# mic.net
KiCad netlist of a schematic drawn in Altium Designer
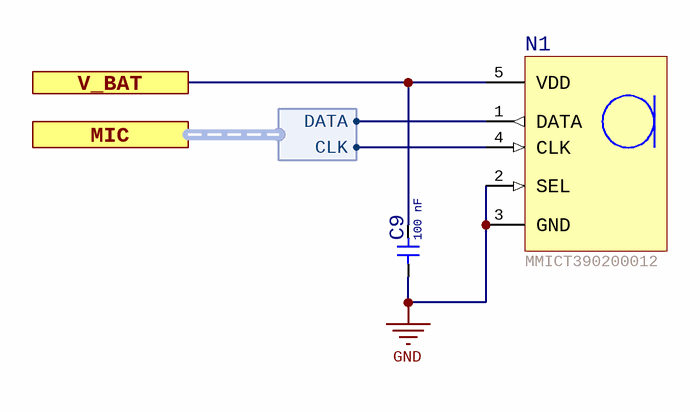
[diagram p0: mic.SchDoc]

(export (version "E")
  (design (tool "Eeschema 10.0.6"))
  (components
    (comp (ref "C9")
      (value "100 nF")
      (footprint "1608C")
      (description "SMD ceramic capacitor")
      (fields (field (name "MANUFACTURER") "Samsung") (field (name "VOLTAGE") "16"))
      (libsource (lib "Contronix") (part "CAP-NP"))
    )
    (comp (ref "N1")
      (value "SNS-MIC-T3902")
      (footprint "SNS-MIC-T3902")
      (description "Bottom Port PDM Low‐Power Multi‐Mode Microphone With High AOP Mode")
      (fields
        (field (name "MANUFACTURER P/N") "MMICT390200012")
        (field (name "MANUFACTURER") "InvenSense")
        (field (name "MANUFACTURER PART NUMBER") "MMICT390200012")
      )
      (libsource (lib "Contronix") (part "SNS-MIC-T3902"))
    )
  )
  (nets
    (net (code "2") (name "/CLK") (class "Default")
      (node (ref "N1") (pin "4") (pinfunction "CLK_4") (pintype "input"))
    )
    (net (code "3") (name "/DATA") (class "Default")
      (node (ref "N1") (pin "1") (pinfunction "DATA_1") (pintype "output"))
    )
    (net (code "4") (name "/V_BAT") (class "Default")
      (node (ref "C9") (pin "2") (pinfunction "2_2") (pintype "passive"))
      (node (ref "N1") (pin "5") (pinfunction "VDD_5") (pintype "power_in"))
    )
    (net (code "6") (name "GND") (class "Default")
      (node (ref "C9") (pin "1") (pinfunction "1_1") (pintype "passive"))
      (node (ref "N1") (pin "2") (pinfunction "SEL_2") (pintype "input"))
      (node (ref "N1") (pin "3") (pinfunction "GND_3") (pintype "power_in"))
    )
  )
)
